# avoccado-avr-pcb-yolandi-panel.net
KiCad netlist of a schematic drawn in EAGLE
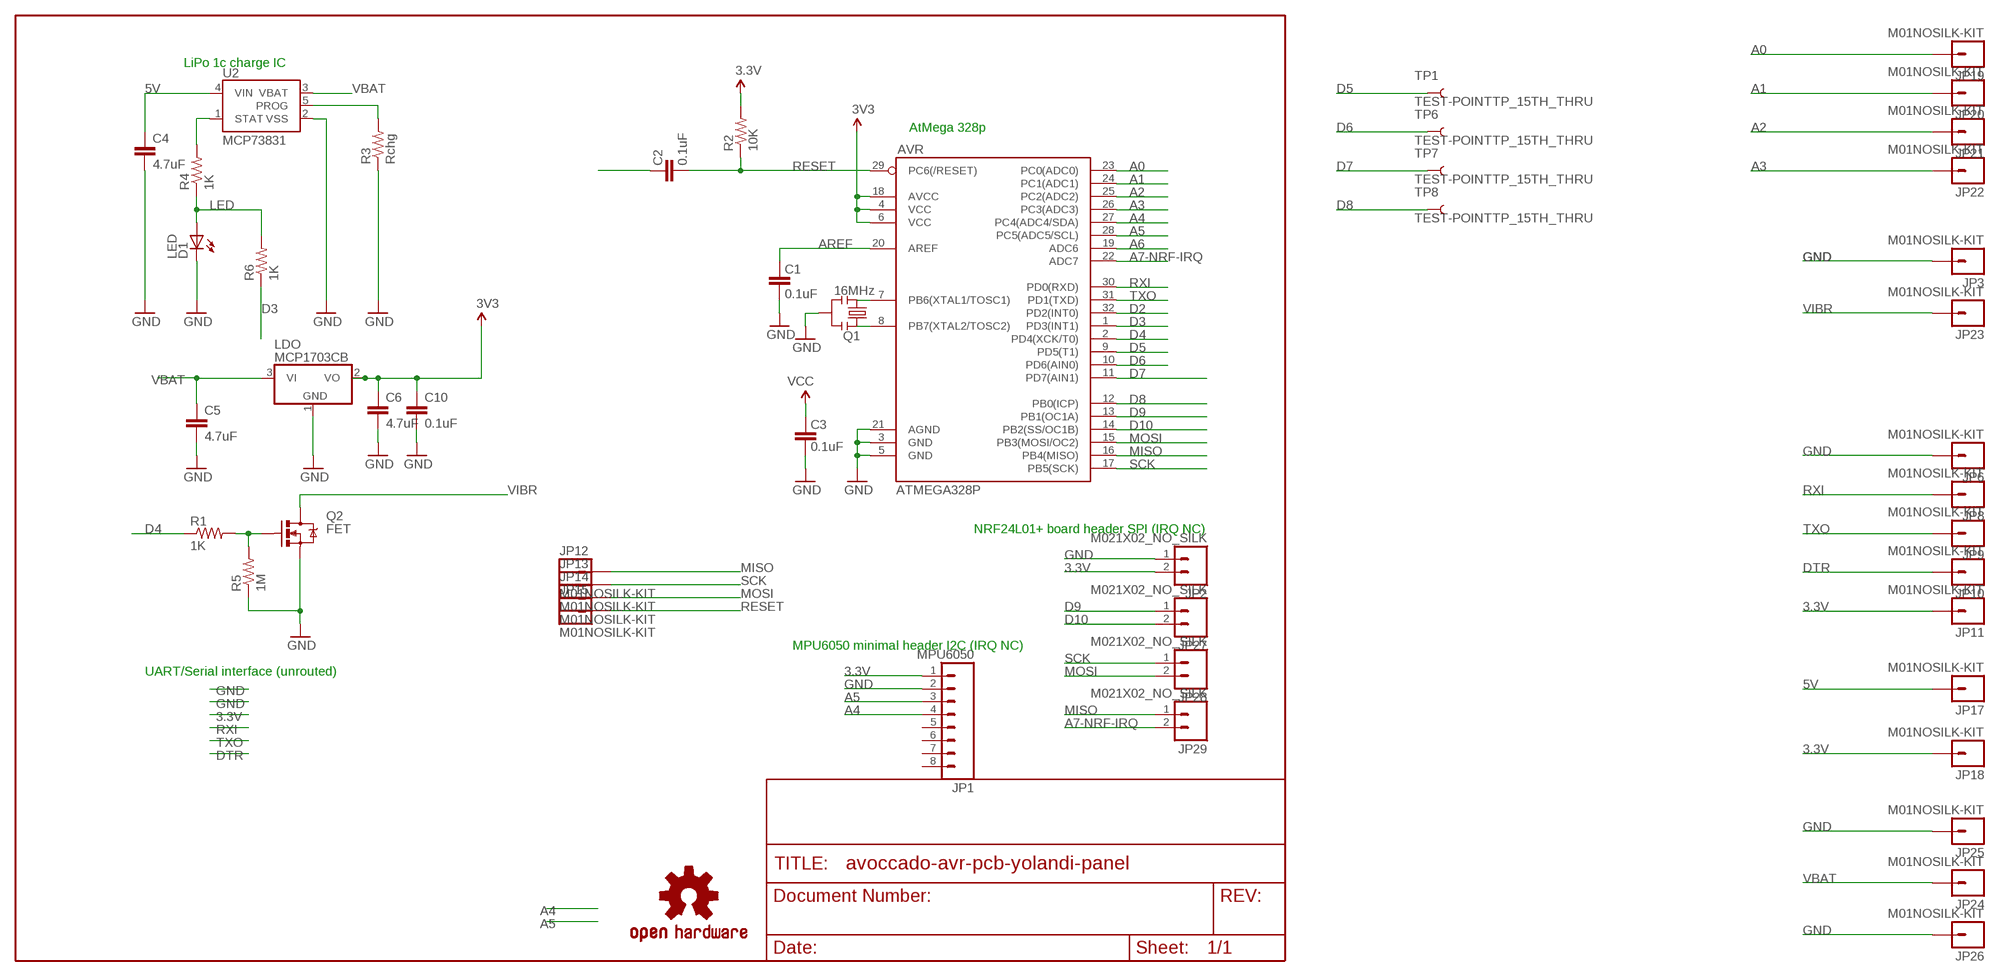
[diagram p0: schematic, sheet 1]

(export (version "E")
  (design (tool "Eeschema 10.0.6"))
  (components
    (comp (ref "AVR")
      (value "ATMEGA328P")
      (footprint "eagle-import:TQFP32-08")
      (libsource (lib "eagle-import") (part "ATMEGA328_SMT"))
    )
    (comp (ref "C1")
      (value "0.1uF")
      (footprint "eagle-import:C0402")
      (libsource (lib "eagle-import") (part "CAP0402"))
    )
    (comp (ref "C2")
      (value "0.1uF")
      (footprint "eagle-import:C0402")
      (libsource (lib "eagle-import") (part "CAP0402"))
    )
    (comp (ref "C3")
      (value "0.1uF")
      (footprint "eagle-import:C0402")
      (libsource (lib "eagle-import") (part "CAP0402"))
    )
    (comp (ref "C4")
      (value "4.7uF")
      (footprint "eagle-import:0603-CAP")
      (libsource (lib "eagle-import") (part "4.7UF-6.3V-10%(0603)0603"))
    )
    (comp (ref "C5")
      (value "4.7uF")
      (footprint "eagle-import:0603-CAP")
      (libsource (lib "eagle-import") (part "4.7UF-6.3V-10%(0603)0603"))
    )
    (comp (ref "C6")
      (value "4.7uF")
      (footprint "eagle-import:0603-CAP")
      (libsource (lib "eagle-import") (part "4.7UF-6.3V-10%(0603)0603"))
    )
    (comp (ref "C10")
      (value "0.1uF")
      (footprint "eagle-import:C0402")
      (libsource (lib "eagle-import") (part "CAP0402"))
    )
    (comp (ref "D1")
      (value "LED")
      (footprint "eagle-import:LED-0603")
      (libsource (lib "eagle-import") (part "LED0603"))
    )
    (comp (ref "JP1")
      (value "MPU6050")
      (footprint "eagle-import:1X08_PIN1_NO_SILK")
      (libsource (lib "eagle-import") (part "M08NO_SILK"))
    )
    (comp (ref "JP2")
      (value "M021X02_NO_SILK")
      (footprint "eagle-import:1X02_NO_SILK")
      (libsource (lib "eagle-import") (part "M021X02_NO_SILK"))
    )
    (comp (ref "JP3")
      (value "M01NOSILK-KIT")
      (footprint "eagle-import:1X01NS-KIT")
      (libsource (lib "eagle-import") (part "M01NOSILK-KIT"))
    )
    (comp (ref "JP6")
      (value "M01NOSILK-KIT")
      (footprint "eagle-import:1X01NS-KIT")
      (libsource (lib "eagle-import") (part "M01NOSILK-KIT"))
    )
    (comp (ref "JP8")
      (value "M01NOSILK-KIT")
      (footprint "eagle-import:1X01NS-KIT")
      (libsource (lib "eagle-import") (part "M01NOSILK-KIT"))
    )
    (comp (ref "JP9")
      (value "M01NOSILK-KIT")
      (footprint "eagle-import:1X01NS-KIT")
      (libsource (lib "eagle-import") (part "M01NOSILK-KIT"))
    )
    (comp (ref "JP10")
      (value "M01NOSILK-KIT")
      (footprint "eagle-import:1X01NS-KIT")
      (libsource (lib "eagle-import") (part "M01NOSILK-KIT"))
    )
    (comp (ref "JP11")
      (value "M01NOSILK-KIT")
      (footprint "eagle-import:1X01NS-KIT")
      (libsource (lib "eagle-import") (part "M01NOSILK-KIT"))
    )
    (comp (ref "JP12")
      (value "M01NOSILK-KIT")
      (footprint "eagle-import:1X01NS-KIT")
      (libsource (lib "eagle-import") (part "M01NOSILK-KIT"))
    )
    (comp (ref "JP13")
      (value "M01NOSILK-KIT")
      (footprint "eagle-import:1X01NS-KIT")
      (libsource (lib "eagle-import") (part "M01NOSILK-KIT"))
    )
    (comp (ref "JP14")
      (value "M01NOSILK-KIT")
      (footprint "eagle-import:1X01NS-KIT")
      (libsource (lib "eagle-import") (part "M01NOSILK-KIT"))
    )
    (comp (ref "JP15")
      (value "M01NOSILK-KIT")
      (footprint "eagle-import:1X01NS-KIT")
      (libsource (lib "eagle-import") (part "M01NOSILK-KIT"))
    )
    (comp (ref "JP17")
      (value "M01NOSILK-KIT")
      (footprint "eagle-import:1X01NS-KIT")
      (libsource (lib "eagle-import") (part "M01NOSILK-KIT"))
    )
    (comp (ref "JP18")
      (value "M01NOSILK-KIT")
      (footprint "eagle-import:1X01NS-KIT")
      (libsource (lib "eagle-import") (part "M01NOSILK-KIT"))
    )
    (comp (ref "JP19")
      (value "M01NOSILK-KIT")
      (footprint "eagle-import:1X01NS-KIT")
      (libsource (lib "eagle-import") (part "M01NOSILK-KIT"))
    )
    (comp (ref "JP20")
      (value "M01NOSILK-KIT")
      (footprint "eagle-import:1X01NS-KIT")
      (libsource (lib "eagle-import") (part "M01NOSILK-KIT"))
    )
    (comp (ref "JP21")
      (value "M01NOSILK-KIT")
      (footprint "eagle-import:1X01NS-KIT")
      (libsource (lib "eagle-import") (part "M01NOSILK-KIT"))
    )
    (comp (ref "JP22")
      (value "M01NOSILK-KIT")
      (footprint "eagle-import:1X01NS-KIT")
      (libsource (lib "eagle-import") (part "M01NOSILK-KIT"))
    )
    (comp (ref "JP23")
      (value "M01NOSILK-KIT")
      (footprint "eagle-import:1X01NS-KIT")
      (libsource (lib "eagle-import") (part "M01NOSILK-KIT"))
    )
    (comp (ref "JP24")
      (value "M01NOSILK-KIT")
      (footprint "eagle-import:1X01NS-KIT")
      (libsource (lib "eagle-import") (part "M01NOSILK-KIT"))
    )
    (comp (ref "JP25")
      (value "M01NOSILK-KIT")
      (footprint "eagle-import:1X01NS-KIT")
      (libsource (lib "eagle-import") (part "M01NOSILK-KIT"))
    )
    (comp (ref "JP26")
      (value "M01NOSILK-KIT")
      (footprint "eagle-import:1X01NS-KIT")
      (libsource (lib "eagle-import") (part "M01NOSILK-KIT"))
    )
    (comp (ref "JP27")
      (value "M021X02_NO_SILK")
      (footprint "eagle-import:1X02_NO_SILK")
      (libsource (lib "eagle-import") (part "M021X02_NO_SILK"))
    )
    (comp (ref "JP28")
      (value "M021X02_NO_SILK")
      (footprint "eagle-import:1X02_NO_SILK")
      (libsource (lib "eagle-import") (part "M021X02_NO_SILK"))
    )
    (comp (ref "JP29")
      (value "M021X02_NO_SILK")
      (footprint "eagle-import:1X02_NO_SILK")
      (libsource (lib "eagle-import") (part "M021X02_NO_SILK"))
    )
    (comp (ref "LDO")
      (value "MCP1703CB")
      (footprint "eagle-import:SOT23")
      (libsource (lib "eagle-import") (part "MCP1703CB"))
    )
    (comp (ref "LOGO1")
      (value "OSHW-LOGOS")
      (footprint "eagle-import:OSHW-LOGO-S")
      (libsource (lib "eagle-import") (part "OSHW-LOGOS"))
    )
    (comp (ref "Q1")
      (value "16MHz")
      (footprint "eagle-import:RESONATOR-SMD")
      (libsource (lib "eagle-import") (part "RESONATORSMD"))
    )
    (comp (ref "Q2")
      (value "FET")
      (footprint "eagle-import:SOT323")
      (libsource (lib "eagle-import") (part "MOSFET-NCHANNEL2N7002PW"))
    )
    (comp (ref "R1")
      (value "1K")
      (footprint "eagle-import:0603-RES")
      (libsource (lib "eagle-import") (part "RESISTOR0603"))
    )
    (comp (ref "R2")
      (value "10K")
      (footprint "eagle-import:0603-RES")
      (libsource (lib "eagle-import") (part "RESISTOR0603"))
    )
    (comp (ref "R3")
      (value "Rchg")
      (footprint "eagle-import:0603-RES")
      (libsource (lib "eagle-import") (part "RESISTOR0603"))
    )
    (comp (ref "R4")
      (value "1K")
      (footprint "eagle-import:0603-RES")
      (libsource (lib "eagle-import") (part "RESISTOR0603"))
    )
    (comp (ref "R5")
      (value "1M")
      (footprint "eagle-import:0603-RES")
      (libsource (lib "eagle-import") (part "RESISTOR0603"))
    )
    (comp (ref "R6")
      (value "1K")
      (footprint "eagle-import:0603-RES")
      (libsource (lib "eagle-import") (part "RESISTOR0603"))
    )
    (comp (ref "TP1")
      (value "TEST-POINTTP_15TH_THRU")
      (footprint "eagle-import:TP_15TH")
      (libsource (lib "eagle-import") (part "TEST-POINTTP_15TH_THRU"))
    )
    (comp (ref "TP6")
      (value "TEST-POINTTP_15TH_THRU")
      (footprint "eagle-import:TP_15TH")
      (libsource (lib "eagle-import") (part "TEST-POINTTP_15TH_THRU"))
    )
    (comp (ref "TP7")
      (value "TEST-POINTTP_15TH_THRU")
      (footprint "eagle-import:TP_15TH")
      (libsource (lib "eagle-import") (part "TEST-POINTTP_15TH_THRU"))
    )
    (comp (ref "TP8")
      (value "TEST-POINTTP_15TH_THRU")
      (footprint "eagle-import:TP_15TH")
      (libsource (lib "eagle-import") (part "TEST-POINTTP_15TH_THRU"))
    )
    (comp (ref "U2")
      (value "MCP73831")
      (footprint "eagle-import:SOT23-5")
      (libsource (lib "eagle-import") (part "MCP73831"))
    )
  )
  (nets
    (net (code "1") (name "/5V") (class "Default")
      (node (ref "C4") (pin "1") (pinfunction "1_1") (pintype "passive"))
      (node (ref "JP17") (pin "1") (pinfunction "1_1") (pintype "passive"))
      (node (ref "U2") (pin "4") (pinfunction "VIN_4") (pintype "power_in"))
    )
    (net (code "2") (name "/A0") (class "Default")
      (node (ref "AVR") (pin "23") (pinfunction "PC0(ADC0)_23") (pintype "bidirectional"))
      (node (ref "JP19") (pin "1") (pinfunction "1_1") (pintype "passive"))
    )
    (net (code "3") (name "/A1") (class "Default")
      (node (ref "AVR") (pin "24") (pinfunction "PC1(ADC1)_24") (pintype "bidirectional"))
      (node (ref "JP20") (pin "1") (pinfunction "1_1") (pintype "passive"))
    )
    (net (code "4") (name "/A2") (class "Default")
      (node (ref "AVR") (pin "25") (pinfunction "PC2(ADC2)_25") (pintype "bidirectional"))
      (node (ref "JP21") (pin "1") (pinfunction "1_1") (pintype "passive"))
    )
    (net (code "5") (name "/A3") (class "Default")
      (node (ref "AVR") (pin "26") (pinfunction "PC3(ADC3)_26") (pintype "bidirectional"))
      (node (ref "JP22") (pin "1") (pinfunction "1_1") (pintype "passive"))
    )
    (net (code "6") (name "/A4") (class "Default")
      (node (ref "AVR") (pin "27") (pinfunction "PC4(ADC4/SDA)_27") (pintype "bidirectional"))
      (node (ref "JP1") (pin "4") (pinfunction "4_4") (pintype "passive"))
    )
    (net (code "7") (name "/A5") (class "Default")
      (node (ref "AVR") (pin "28") (pinfunction "PC5(ADC5/SCL)_28") (pintype "bidirectional"))
      (node (ref "JP1") (pin "3") (pinfunction "3_3") (pintype "passive"))
    )
    (net (code "8") (name "/A6") (class "Default")
      (node (ref "AVR") (pin "19") (pinfunction "ADC6_19") (pintype "bidirectional"))
    )
    (net (code "9") (name "/A7-NRF-IRQ") (class "Default")
      (node (ref "AVR") (pin "22") (pinfunction "ADC7_22") (pintype "bidirectional"))
      (node (ref "JP29") (pin "2") (pinfunction "2_2") (pintype "passive"))
    )
    (net (code "10") (name "/AREF") (class "Default")
      (node (ref "AVR") (pin "20") (pinfunction "AREF_20") (pintype "bidirectional"))
      (node (ref "C1") (pin "2") (pinfunction "2_2") (pintype "passive"))
    )
    (net (code "11") (name "/D2") (class "Default")
      (node (ref "AVR") (pin "32") (pinfunction "PD2(INT0)_32") (pintype "bidirectional"))
    )
    (net (code "12") (name "/D3") (class "Default")
      (node (ref "AVR") (pin "1") (pinfunction "PD3(INT1)_1") (pintype "bidirectional"))
      (node (ref "R6") (pin "1") (pinfunction "1_1") (pintype "passive"))
    )
    (net (code "13") (name "/D4") (class "Default")
      (node (ref "AVR") (pin "2") (pinfunction "PD4(XCK/T0)_2") (pintype "bidirectional"))
      (node (ref "R1") (pin "1") (pinfunction "1_1") (pintype "passive"))
    )
    (net (code "14") (name "/D5") (class "Default")
      (node (ref "AVR") (pin "9") (pinfunction "PD5(T1)_9") (pintype "bidirectional"))
      (node (ref "TP1") (pin "P$1") (pinfunction "1_P$1") (pintype "bidirectional"))
    )
    (net (code "15") (name "/D6") (class "Default")
      (node (ref "AVR") (pin "10") (pinfunction "PD6(AIN0)_10") (pintype "bidirectional"))
      (node (ref "TP6") (pin "P$1") (pinfunction "1_P$1") (pintype "bidirectional"))
    )
    (net (code "16") (name "/D7") (class "Default")
      (node (ref "AVR") (pin "11") (pinfunction "PD7(AIN1)_11") (pintype "bidirectional"))
      (node (ref "TP7") (pin "P$1") (pinfunction "1_P$1") (pintype "bidirectional"))
    )
    (net (code "17") (name "/D8") (class "Default")
      (node (ref "AVR") (pin "12") (pinfunction "PB0(ICP)_12") (pintype "bidirectional"))
      (node (ref "TP8") (pin "P$1") (pinfunction "1_P$1") (pintype "bidirectional"))
    )
    (net (code "18") (name "/D9") (class "Default")
      (node (ref "AVR") (pin "13") (pinfunction "PB1(OC1A)_13") (pintype "bidirectional"))
      (node (ref "JP27") (pin "1") (pinfunction "1_1") (pintype "passive"))
    )
    (net (code "19") (name "/D10") (class "Default")
      (node (ref "AVR") (pin "14") (pinfunction "PB2(SS/OC1B)_14") (pintype "bidirectional"))
      (node (ref "JP27") (pin "2") (pinfunction "2_2") (pintype "passive"))
    )
    (net (code "20") (name "/DTR") (class "Default")
      (node (ref "C2") (pin "2") (pinfunction "2_2") (pintype "passive"))
      (node (ref "JP10") (pin "1") (pinfunction "1_1") (pintype "passive"))
    )
    (net (code "21") (name "/LED") (class "Default")
      (node (ref "D1") (pin "A") (pinfunction "A_A") (pintype "passive"))
      (node (ref "R4") (pin "1") (pinfunction "1_1") (pintype "passive"))
      (node (ref "R6") (pin "2") (pinfunction "2_2") (pintype "passive"))
    )
    (net (code "22") (name "/MISO") (class "Default")
      (node (ref "AVR") (pin "16") (pinfunction "PB4(MISO)_16") (pintype "bidirectional"))
      (node (ref "JP12") (pin "1") (pinfunction "1_1") (pintype "passive"))
      (node (ref "JP29") (pin "1") (pinfunction "1_1") (pintype "passive"))
    )
    (net (code "23") (name "/MOSI") (class "Default")
      (node (ref "AVR") (pin "15") (pinfunction "PB3(MOSI/OC2)_15") (pintype "bidirectional"))
      (node (ref "JP14") (pin "1") (pinfunction "1_1") (pintype "passive"))
      (node (ref "JP28") (pin "2") (pinfunction "2_2") (pintype "passive"))
    )
    (net (code "24") (name "/RESET") (class "Default")
      (node (ref "AVR") (pin "29") (pinfunction "PC6(/RESET)_29") (pintype "bidirectional"))
      (node (ref "C2") (pin "1") (pinfunction "1_1") (pintype "passive"))
      (node (ref "JP15") (pin "1") (pinfunction "1_1") (pintype "passive"))
      (node (ref "R2") (pin "1") (pinfunction "1_1") (pintype "passive"))
    )
    (net (code "25") (name "/RXI") (class "Default")
      (node (ref "AVR") (pin "30") (pinfunction "PD0(RXD)_30") (pintype "bidirectional"))
      (node (ref "JP8") (pin "1") (pinfunction "1_1") (pintype "passive"))
    )
    (net (code "26") (name "/SCK") (class "Default")
      (node (ref "AVR") (pin "17") (pinfunction "PB5(SCK)_17") (pintype "bidirectional"))
      (node (ref "JP13") (pin "1") (pinfunction "1_1") (pintype "passive"))
      (node (ref "JP28") (pin "1") (pinfunction "1_1") (pintype "passive"))
    )
    (net (code "27") (name "/TXO") (class "Default")
      (node (ref "AVR") (pin "31") (pinfunction "PD1(TXD)_31") (pintype "bidirectional"))
      (node (ref "JP9") (pin "1") (pinfunction "1_1") (pintype "passive"))
    )
    (net (code "28") (name "/VBAT") (class "Default")
      (node (ref "C5") (pin "1") (pinfunction "1_1") (pintype "passive"))
      (node (ref "JP24") (pin "1") (pinfunction "1_1") (pintype "passive"))
      (node (ref "LDO") (pin "3") (pinfunction "VI_3") (pintype "input"))
      (node (ref "U2") (pin "3") (pinfunction "VBAT_3") (pintype "power_in"))
    )
    (net (code "29") (name "/VIBR") (class "Default")
      (node (ref "JP23") (pin "1") (pinfunction "1_1") (pintype "passive"))
      (node (ref "Q2") (pin "3") (pinfunction "D_3") (pintype "passive"))
    )
    (net (code "30") (name "3.3V") (class "Default")
      (node (ref "AVR") (pin "18") (pinfunction "AVCC_18") (pintype "bidirectional"))
      (node (ref "AVR") (pin "4") (pinfunction "VCC_4") (pintype "bidirectional"))
      (node (ref "AVR") (pin "6") (pinfunction "VCC_6") (pintype "bidirectional"))
      (node (ref "C10") (pin "1") (pinfunction "1_1") (pintype "passive"))
      (node (ref "C3") (pin "2") (pinfunction "2_2") (pintype "passive"))
      (node (ref "C6") (pin "1") (pinfunction "1_1") (pintype "passive"))
      (node (ref "JP1") (pin "1") (pinfunction "1_1") (pintype "passive"))
      (node (ref "JP11") (pin "1") (pinfunction "1_1") (pintype "passive"))
      (node (ref "JP18") (pin "1") (pinfunction "1_1") (pintype "passive"))
      (node (ref "JP2") (pin "2") (pinfunction "2_2") (pintype "passive"))
      (node (ref "LDO") (pin "2") (pinfunction "VO_2") (pintype "passive"))
      (node (ref "R2") (pin "2") (pinfunction "2_2") (pintype "passive"))
    )
    (net (code "31") (name "GND") (class "Default")
      (node (ref "AVR") (pin "21") (pinfunction "AGND_21") (pintype "bidirectional"))
      (node (ref "AVR") (pin "3") (pinfunction "GND_3") (pintype "bidirectional"))
      (node (ref "AVR") (pin "5") (pinfunction "GND_5") (pintype "bidirectional"))
      (node (ref "C1") (pin "1") (pinfunction "1_1") (pintype "passive"))
      (node (ref "C10") (pin "2") (pinfunction "2_2") (pintype "passive"))
      (node (ref "C3") (pin "1") (pinfunction "1_1") (pintype "passive"))
      (node (ref "C4") (pin "2") (pinfunction "2_2") (pintype "passive"))
      (node (ref "C5") (pin "2") (pinfunction "2_2") (pintype "passive"))
      (node (ref "C6") (pin "2") (pinfunction "2_2") (pintype "passive"))
      (node (ref "D1") (pin "C") (pinfunction "C_C") (pintype "passive"))
      (node (ref "JP1") (pin "2") (pinfunction "2_2") (pintype "passive"))
      (node (ref "JP2") (pin "1") (pinfunction "1_1") (pintype "passive"))
      (node (ref "JP25") (pin "1") (pinfunction "1_1") (pintype "passive"))
      (node (ref "JP26") (pin "1") (pinfunction "1_1") (pintype "passive"))
      (node (ref "JP3") (pin "1") (pinfunction "1_1") (pintype "passive"))
      (node (ref "JP6") (pin "1") (pinfunction "1_1") (pintype "passive"))
      (node (ref "LDO") (pin "1") (pinfunction "GND_1") (pintype "passive"))
      (node (ref "Q1") (pin "2") (pinfunction "2_2") (pintype "passive"))
      (node (ref "Q2") (pin "2") (pinfunction "S_2") (pintype "passive"))
      (node (ref "R3") (pin "1") (pinfunction "1_1") (pintype "passive"))
      (node (ref "R5") (pin "1") (pinfunction "1_1") (pintype "passive"))
      (node (ref "U2") (pin "2") (pinfunction "VSS_2") (pintype "power_in"))
    )
    (net (code "32") (name "Net-(AVR-PB6(XTAL1{slash}TOSC1))") (class "Default")
      (node (ref "AVR") (pin "7") (pinfunction "PB6(XTAL1/TOSC1)_7") (pintype "bidirectional"))
      (node (ref "Q1") (pin "3") (pinfunction "3_3") (pintype "passive"))
    )
    (net (code "33") (name "Net-(AVR-PB7(XTAL2{slash}TOSC2))") (class "Default")
      (node (ref "AVR") (pin "8") (pinfunction "PB7(XTAL2/TOSC2)_8") (pintype "bidirectional"))
      (node (ref "Q1") (pin "1") (pinfunction "1_1") (pintype "passive"))
    )
    (net (code "34") (name "Net-(Q2-G)") (class "Default")
      (node (ref "Q2") (pin "1") (pinfunction "G_1") (pintype "passive"))
      (node (ref "R1") (pin "2") (pinfunction "2_2") (pintype "passive"))
      (node (ref "R5") (pin "2") (pinfunction "2_2") (pintype "passive"))
    )
    (net (code "35") (name "Net-(U2-PROG)") (class "Default")
      (node (ref "R3") (pin "2") (pinfunction "2_2") (pintype "passive"))
      (node (ref "U2") (pin "5") (pinfunction "PROG_5") (pintype "input"))
    )
    (net (code "36") (name "Net-(U2-STAT)") (class "Default")
      (node (ref "R4") (pin "2") (pinfunction "2_2") (pintype "passive"))
      (node (ref "U2") (pin "1") (pinfunction "STAT_1") (pintype "output"))
    )
    (net (code "37") (name "unconnected-(JP1-Pad5)") (class "Default")
      (node (ref "JP1") (pin "5") (pinfunction "5_5") (pintype "passive"))
    )
    (net (code "38") (name "unconnected-(JP1-Pad6)") (class "Default")
      (node (ref "JP1") (pin "6") (pinfunction "6_6") (pintype "passive"))
    )
    (net (code "39") (name "unconnected-(JP1-Pad7)") (class "Default")
      (node (ref "JP1") (pin "7") (pinfunction "7_7") (pintype "passive"))
    )
    (net (code "40") (name "unconnected-(JP1-Pad8)") (class "Default")
      (node (ref "JP1") (pin "8") (pinfunction "8_8") (pintype "passive"))
    )
  )
)
